# untitled.net
KiCad netlist of a schematic drawn in EAGLE
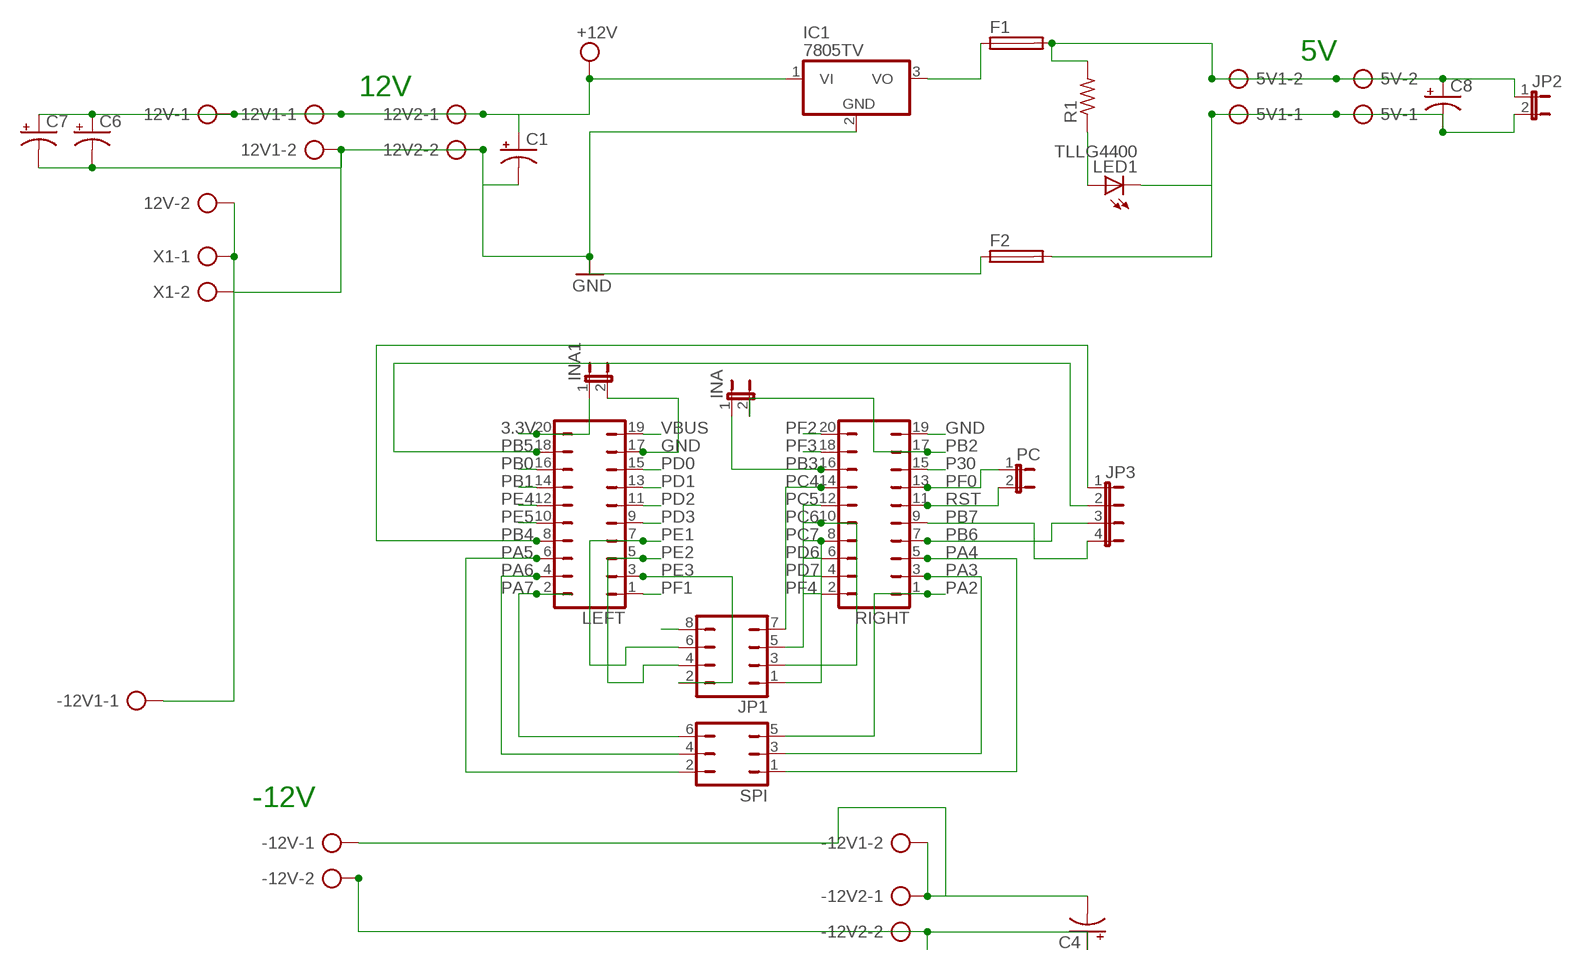
[diagram p0: schematic, sheet 1]

(export (version "E")
  (design (tool "Eeschema 10.0.6"))
  (components
    (comp (ref "-12V")
      (value "AK300/2")
      (footprint "eagle-import:AK300_2")
      (libsource (lib "eagle-import") (part "AK300/2"))
    )
    (comp (ref "-12V1")
      (value "AK300/2")
      (footprint "eagle-import:AK300_2")
      (libsource (lib "eagle-import") (part "AK300/2"))
    )
    (comp (ref "-12V2")
      (value "AK300/2")
      (footprint "eagle-import:AK300_2")
      (libsource (lib "eagle-import") (part "AK300/2"))
    )
    (comp (ref "5V")
      (value "AK300/2")
      (footprint "eagle-import:AK300_2")
      (libsource (lib "eagle-import") (part "AK300/2"))
    )
    (comp (ref "5V1")
      (value "AK300/2")
      (footprint "eagle-import:AK300_2")
      (libsource (lib "eagle-import") (part "AK300/2"))
    )
    (comp (ref "12V")
      (value "AK300/2")
      (footprint "eagle-import:AK300_2")
      (libsource (lib "eagle-import") (part "AK300/2"))
    )
    (comp (ref "12V1")
      (value "AK300/2")
      (footprint "eagle-import:AK300_2")
      (libsource (lib "eagle-import") (part "AK300/2"))
    )
    (comp (ref "12V2")
      (value "AK300/2")
      (footprint "eagle-import:AK300_2")
      (libsource (lib "eagle-import") (part "AK300/2"))
    )
    (comp (ref "C1")
      (value "CPOL-USE3.5-10")
      (footprint "eagle-import:E3,5-10")
      (libsource (lib "eagle-import") (part "CPOL-USE3.5-10"))
    )
    (comp (ref "C4")
      (value "CPOL-USE3.5-10")
      (footprint "eagle-import:E3,5-10")
      (libsource (lib "eagle-import") (part "CPOL-USE3.5-10"))
    )
    (comp (ref "C6")
      (value "CPOL-USE3.5-10")
      (footprint "eagle-import:E3,5-10")
      (libsource (lib "eagle-import") (part "CPOL-USE3.5-10"))
    )
    (comp (ref "C7")
      (value "CPOL-USE3.5-10")
      (footprint "eagle-import:E3,5-10")
      (libsource (lib "eagle-import") (part "CPOL-USE3.5-10"))
    )
    (comp (ref "C8")
      (value "CPOL-USE3.5-10")
      (footprint "eagle-import:E3,5-10")
      (libsource (lib "eagle-import") (part "CPOL-USE3.5-10"))
    )
    (comp (ref "F1")
      (value "GSH15")
      (footprint "eagle-import:GSH15")
      (fields (field (name "MPN") "64900001039"))
      (libsource (lib "eagle-import") (part "GSH15"))
    )
    (comp (ref "F2")
      (value "GSH15")
      (footprint "eagle-import:GSH15")
      (fields (field (name "MPN") "64900001039"))
      (libsource (lib "eagle-import") (part "GSH15"))
    )
    (comp (ref "IC1")
      (value "7805TV")
      (footprint "eagle-import:TO220V")
      (libsource (lib "eagle-import") (part "78TV05"))
    )
    (comp (ref "INA")
      (value "JP1E")
      (footprint "eagle-import:JP1")
      (libsource (lib "eagle-import") (part "JP1E"))
    )
    (comp (ref "INA1")
      (value "JP1E")
      (footprint "eagle-import:JP1")
      (libsource (lib "eagle-import") (part "JP1E"))
    )
    (comp (ref "JP1")
      (value "JP4Q")
      (footprint "eagle-import:JP4Q")
      (libsource (lib "eagle-import") (part "JP4Q"))
    )
    (comp (ref "JP2")
      (value "JP1E")
      (footprint "eagle-import:JP1")
      (libsource (lib "eagle-import") (part "JP1E"))
    )
    (comp (ref "JP3")
      (value "JP4E")
      (footprint "eagle-import:JP4")
      (libsource (lib "eagle-import") (part "JP4E"))
    )
    (comp (ref "LED1")
      (value "TLLG4400")
      (footprint "eagle-import:LED3MM")
      (fields (field (name "MF") "VISHAY SEMICONDUCTOR"))
      (libsource (lib "eagle-import") (part "TLLG4400"))
    )
    (comp (ref "LEFT")
      (value "JP10Q")
      (footprint "eagle-import:JP10Q")
      (libsource (lib "eagle-import") (part "JP10Q"))
    )
    (comp (ref "PC")
      (value "JP1E")
      (footprint "eagle-import:JP1")
      (libsource (lib "eagle-import") (part "JP1E"))
    )
    (comp (ref "R1")
      (value "R-US_0207/10")
      (footprint "eagle-import:0207_10")
      (libsource (lib "eagle-import") (part "R-US_0207/10"))
    )
    (comp (ref "RIGHT")
      (value "JP10Q")
      (footprint "eagle-import:JP10Q")
      (libsource (lib "eagle-import") (part "JP10Q"))
    )
    (comp (ref "SPI")
      (value "JP3Q")
      (footprint "eagle-import:JP3Q")
      (libsource (lib "eagle-import") (part "JP3Q"))
    )
    (comp (ref "X1")
      (value "AK300/2")
      (footprint "eagle-import:AK300_2")
      (libsource (lib "eagle-import") (part "AK300/2"))
    )
  )
  (nets
    (net (code "1") (name "+12V") (class "Default")
      (node (ref "12V") (pin "1") (pinfunction "KL_1") (pintype "passive"))
      (node (ref "12V1") (pin "1") (pinfunction "KL_1") (pintype "passive"))
      (node (ref "12V2") (pin "1") (pinfunction "KL_1") (pintype "passive"))
      (node (ref "C1") (pin "+") (pinfunction "+_+") (pintype "passive"))
      (node (ref "C6") (pin "+") (pinfunction "+_+") (pintype "passive"))
      (node (ref "C7") (pin "+") (pinfunction "+_+") (pintype "passive"))
      (node (ref "IC1") (pin "1") (pinfunction "VI_1") (pintype "input"))
    )
    (net (code "2") (name "/3.3V") (class "Default")
      (node (ref "INA1") (pin "1") (pinfunction "1_1") (pintype "passive"))
      (node (ref "LEFT") (pin "20") (pinfunction "20_20") (pintype "passive"))
    )
    (net (code "3") (name "/P30") (class "Default")
      (node (ref "RIGHT") (pin "15") (pinfunction "15_15") (pintype "passive"))
    )
    (net (code "4") (name "/PA2") (class "Default")
      (node (ref "RIGHT") (pin "1") (pinfunction "1_1") (pintype "passive"))
      (node (ref "SPI") (pin "5") (pinfunction "5_5") (pintype "passive"))
    )
    (net (code "5") (name "/PA3") (class "Default")
      (node (ref "RIGHT") (pin "3") (pinfunction "3_3") (pintype "passive"))
      (node (ref "SPI") (pin "3") (pinfunction "3_3") (pintype "passive"))
    )
    (net (code "6") (name "/PA4") (class "Default")
      (node (ref "RIGHT") (pin "5") (pinfunction "5_5") (pintype "passive"))
      (node (ref "SPI") (pin "1") (pinfunction "1_1") (pintype "passive"))
    )
    (net (code "7") (name "/PA5") (class "Default")
      (node (ref "LEFT") (pin "6") (pinfunction "6_6") (pintype "passive"))
      (node (ref "SPI") (pin "2") (pinfunction "2_2") (pintype "passive"))
    )
    (net (code "8") (name "/PA6") (class "Default")
      (node (ref "LEFT") (pin "4") (pinfunction "4_4") (pintype "passive"))
      (node (ref "SPI") (pin "4") (pinfunction "4_4") (pintype "passive"))
    )
    (net (code "9") (name "/PA7") (class "Default")
      (node (ref "LEFT") (pin "2") (pinfunction "2_2") (pintype "passive"))
      (node (ref "SPI") (pin "6") (pinfunction "6_6") (pintype "passive"))
    )
    (net (code "10") (name "/PB0") (class "Default")
      (node (ref "LEFT") (pin "16") (pinfunction "16_16") (pintype "passive"))
    )
    (net (code "11") (name "/PB1") (class "Default")
      (node (ref "LEFT") (pin "14") (pinfunction "14_14") (pintype "passive"))
    )
    (net (code "12") (name "/PB2") (class "Default")
      (node (ref "INA") (pin "2") (pinfunction "2_2") (pintype "passive"))
      (node (ref "RIGHT") (pin "17") (pinfunction "17_17") (pintype "passive"))
    )
    (net (code "13") (name "/PB3") (class "Default")
      (node (ref "INA") (pin "1") (pinfunction "1_1") (pintype "passive"))
      (node (ref "RIGHT") (pin "16") (pinfunction "16_16") (pintype "passive"))
    )
    (net (code "14") (name "/PB4") (class "Default")
      (node (ref "JP3") (pin "1") (pinfunction "1_1") (pintype "passive"))
      (node (ref "LEFT") (pin "8") (pinfunction "8_8") (pintype "passive"))
    )
    (net (code "15") (name "/PB5") (class "Default")
      (node (ref "JP3") (pin "2") (pinfunction "2_2") (pintype "passive"))
      (node (ref "LEFT") (pin "18") (pinfunction "18_18") (pintype "passive"))
    )
    (net (code "16") (name "/PB6") (class "Default")
      (node (ref "JP3") (pin "3") (pinfunction "3_3") (pintype "passive"))
      (node (ref "RIGHT") (pin "7") (pinfunction "7_7") (pintype "passive"))
    )
    (net (code "17") (name "/PB7") (class "Default")
      (node (ref "JP3") (pin "4") (pinfunction "4_4") (pintype "passive"))
      (node (ref "RIGHT") (pin "9") (pinfunction "9_9") (pintype "passive"))
    )
    (net (code "18") (name "/PC4") (class "Default")
      (node (ref "JP1") (pin "7") (pinfunction "7_7") (pintype "passive"))
      (node (ref "RIGHT") (pin "14") (pinfunction "14_14") (pintype "passive"))
    )
    (net (code "19") (name "/PC5") (class "Default")
      (node (ref "JP1") (pin "5") (pinfunction "5_5") (pintype "passive"))
      (node (ref "RIGHT") (pin "12") (pinfunction "12_12") (pintype "passive"))
    )
    (net (code "20") (name "/PC6") (class "Default")
      (node (ref "JP1") (pin "3") (pinfunction "3_3") (pintype "passive"))
      (node (ref "RIGHT") (pin "10") (pinfunction "10_10") (pintype "passive"))
    )
    (net (code "21") (name "/PC7") (class "Default")
      (node (ref "JP1") (pin "1") (pinfunction "1_1") (pintype "passive"))
      (node (ref "RIGHT") (pin "8") (pinfunction "8_8") (pintype "passive"))
    )
    (net (code "22") (name "/PD0") (class "Default")
      (node (ref "LEFT") (pin "15") (pinfunction "15_15") (pintype "passive"))
    )
    (net (code "23") (name "/PD1") (class "Default")
      (node (ref "LEFT") (pin "13") (pinfunction "13_13") (pintype "passive"))
    )
    (net (code "24") (name "/PD2") (class "Default")
      (node (ref "LEFT") (pin "11") (pinfunction "11_11") (pintype "passive"))
    )
    (net (code "25") (name "/PD3") (class "Default")
      (node (ref "LEFT") (pin "9") (pinfunction "9_9") (pintype "passive"))
    )
    (net (code "26") (name "/PD6") (class "Default")
      (node (ref "RIGHT") (pin "6") (pinfunction "6_6") (pintype "passive"))
    )
    (net (code "27") (name "/PD7") (class "Default")
      (node (ref "RIGHT") (pin "4") (pinfunction "4_4") (pintype "passive"))
    )
    (net (code "28") (name "/PE1") (class "Default")
      (node (ref "JP1") (pin "6") (pinfunction "6_6") (pintype "passive"))
      (node (ref "LEFT") (pin "7") (pinfunction "7_7") (pintype "passive"))
    )
    (net (code "29") (name "/PE2") (class "Default")
      (node (ref "JP1") (pin "4") (pinfunction "4_4") (pintype "passive"))
      (node (ref "LEFT") (pin "5") (pinfunction "5_5") (pintype "passive"))
    )
    (net (code "30") (name "/PE3") (class "Default")
      (node (ref "JP1") (pin "2") (pinfunction "2_2") (pintype "passive"))
      (node (ref "LEFT") (pin "3") (pinfunction "3_3") (pintype "passive"))
    )
    (net (code "31") (name "/PE4") (class "Default")
      (node (ref "LEFT") (pin "12") (pinfunction "12_12") (pintype "passive"))
    )
    (net (code "32") (name "/PE5") (class "Default")
      (node (ref "LEFT") (pin "10") (pinfunction "10_10") (pintype "passive"))
    )
    (net (code "33") (name "/PF0") (class "Default")
      (node (ref "PC") (pin "1") (pinfunction "1_1") (pintype "passive"))
      (node (ref "RIGHT") (pin "13") (pinfunction "13_13") (pintype "passive"))
    )
    (net (code "34") (name "/PF1") (class "Default")
      (node (ref "LEFT") (pin "1") (pinfunction "1_1") (pintype "passive"))
    )
    (net (code "35") (name "/PF2") (class "Default")
      (node (ref "RIGHT") (pin "20") (pinfunction "20_20") (pintype "passive"))
    )
    (net (code "36") (name "/PF3") (class "Default")
      (node (ref "RIGHT") (pin "18") (pinfunction "18_18") (pintype "passive"))
    )
    (net (code "37") (name "/PF4") (class "Default")
      (node (ref "RIGHT") (pin "2") (pinfunction "2_2") (pintype "passive"))
    )
    (net (code "38") (name "/RST") (class "Default")
      (node (ref "PC") (pin "2") (pinfunction "2_2") (pintype "passive"))
      (node (ref "RIGHT") (pin "11") (pinfunction "11_11") (pintype "passive"))
    )
    (net (code "39") (name "/VBUS") (class "Default")
      (node (ref "LEFT") (pin "19") (pinfunction "19_19") (pintype "passive"))
    )
    (net (code "40") (name "GND") (class "Default")
      (node (ref "-12V") (pin "2") (pinfunction "KL_2") (pintype "passive"))
      (node (ref "-12V2") (pin "2") (pinfunction "KL_2") (pintype "passive"))
      (node (ref "12V1") (pin "2") (pinfunction "KL_2") (pintype "passive"))
      (node (ref "12V2") (pin "2") (pinfunction "KL_2") (pintype "passive"))
      (node (ref "C1") (pin "-") (pinfunction "-_-") (pintype "passive"))
      (node (ref "C4") (pin "+") (pinfunction "+_+") (pintype "passive"))
      (node (ref "C6") (pin "-") (pinfunction "-_-") (pintype "passive"))
      (node (ref "C7") (pin "-") (pinfunction "-_-") (pintype "passive"))
      (node (ref "F2") (pin "1") (pinfunction "1_1") (pintype "passive"))
      (node (ref "IC1") (pin "2") (pinfunction "GND_2") (pintype "passive"))
      (node (ref "INA1") (pin "2") (pinfunction "2_2") (pintype "passive"))
      (node (ref "JP1") (pin "8") (pinfunction "8_8") (pintype "passive"))
      (node (ref "LEFT") (pin "17") (pinfunction "17_17") (pintype "passive"))
      (node (ref "RIGHT") (pin "19") (pinfunction "19_19") (pintype "passive"))
      (node (ref "X1") (pin "2") (pinfunction "KL_2") (pintype "passive"))
    )
    (net (code "41") (name "Net-(-12V1A-KL)") (class "Default")
      (node (ref "-12V1") (pin "1") (pinfunction "KL_1") (pintype "passive"))
      (node (ref "12V") (pin "2") (pinfunction "KL_2") (pintype "passive"))
      (node (ref "X1") (pin "1") (pinfunction "KL_1") (pintype "passive"))
    )
    (net (code "42") (name "Net-(-12V1B-KL)") (class "Default")
      (node (ref "-12V") (pin "1") (pinfunction "KL_1") (pintype "passive"))
      (node (ref "-12V1") (pin "2") (pinfunction "KL_2") (pintype "passive"))
      (node (ref "-12V2") (pin "1") (pinfunction "KL_1") (pintype "passive"))
      (node (ref "C4") (pin "-") (pinfunction "-_-") (pintype "passive"))
    )
    (net (code "43") (name "Net-(5V1A-KL)") (class "Default")
      (node (ref "5V") (pin "1") (pinfunction "KL_1") (pintype "passive"))
      (node (ref "5V1") (pin "1") (pinfunction "KL_1") (pintype "passive"))
      (node (ref "C8") (pin "-") (pinfunction "-_-") (pintype "passive"))
      (node (ref "F2") (pin "2") (pinfunction "2_2") (pintype "passive"))
      (node (ref "JP2") (pin "2") (pinfunction "2_2") (pintype "passive"))
      (node (ref "LED1") (pin "K") (pinfunction "C_K") (pintype "passive"))
    )
    (net (code "44") (name "Net-(5V1B-KL)") (class "Default")
      (node (ref "5V") (pin "2") (pinfunction "KL_2") (pintype "passive"))
      (node (ref "5V1") (pin "2") (pinfunction "KL_2") (pintype "passive"))
      (node (ref "C8") (pin "+") (pinfunction "+_+") (pintype "passive"))
      (node (ref "F1") (pin "2") (pinfunction "2_2") (pintype "passive"))
      (node (ref "JP2") (pin "1") (pinfunction "1_1") (pintype "passive"))
      (node (ref "R1") (pin "2") (pinfunction "2_2") (pintype "passive"))
    )
    (net (code "45") (name "Net-(IC1-VO)") (class "Default")
      (node (ref "F1") (pin "1") (pinfunction "1_1") (pintype "passive"))
      (node (ref "IC1") (pin "3") (pinfunction "VO_3") (pintype "passive"))
    )
    (net (code "46") (name "Net-(LED1-PadA)") (class "Default")
      (node (ref "LED1") (pin "A") (pinfunction "A_A") (pintype "passive"))
      (node (ref "R1") (pin "1") (pinfunction "1_1") (pintype "passive"))
    )
  )
)
